# system_electric_diagram__1.net
KiCad netlist of a schematic drawn in Altium Designer
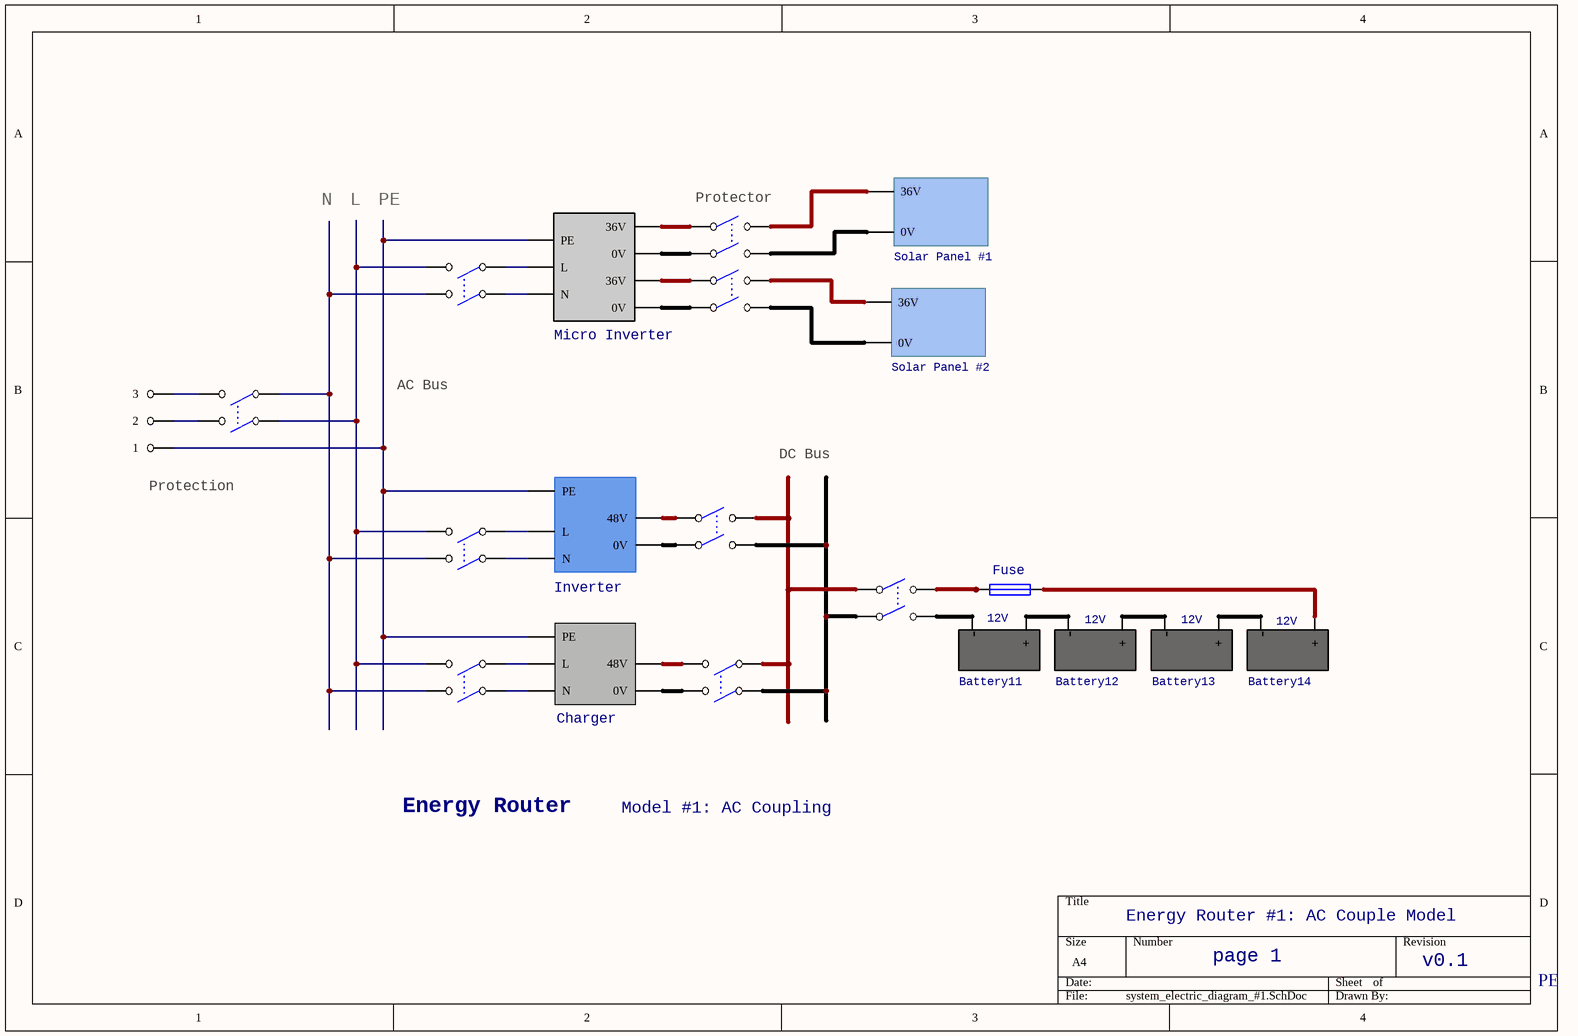
[diagram p0: system_electric_diagram_#1.SchDoc]

(export (version "E")
  (design (tool "Eeschema 10.0.6"))
  (components
    (comp (ref "Battery11") (value "12V") (libsource (lib "0_Schlib-电源柜") (part "1_BAT_12V")))
    (comp (ref "Battery12") (value "12V") (libsource (lib "0_Schlib-电源柜") (part "1_BAT_12V")))
    (comp (ref "Battery13") (value "12V") (libsource (lib "0_Schlib-电源柜") (part "1_BAT_12V")))
    (comp (ref "Battery14") (value "12V") (libsource (lib "0_Schlib-电源柜") (part "1_BAT_12V")))
    (comp (ref "F11") (value "Fuse") (footprint "FUSE1") (libsource (lib "常用元件库") (part "FUSE")))
    (comp (ref "JP01")
      (value "3 HEADER")
      (description "3 Pin Header")
      (libsource (lib "myzou") (part "3 HEADER"))
    )
    (comp (ref "K2") (value "Switch") (libsource (lib "开关") (part "SW-DPST")))
    (comp (ref "K3") (value "Switch") (libsource (lib "开关") (part "SW-DPST")))
    (comp (ref "K4") (value "Switch") (libsource (lib "开关") (part "SW-DPST")))
    (comp (ref "K5") (value "Switch") (libsource (lib "开关") (part "SW-DPST")))
    (comp (ref "K6") (value "Switch") (libsource (lib "开关") (part "SW-DPST")))
    (comp (ref "K7") (value "Switch") (libsource (lib "开关") (part "SW-DPST")))
    (comp (ref "K10") (value "Switch") (libsource (lib "开关") (part "SW-DPST")))
    (comp (ref "K11") (value "Switch") (libsource (lib "开关") (part "SW-DPST")))
    (comp (ref "K12") (value "Switch") (libsource (lib "开关") (part "SW-DPST")))
    (comp (ref "U1") (value "Micro Inverter") (libsource (lib "0_Schlib-电源柜") (part "11_Micro_Inverter_2")))
    (comp (ref "U2") (value "Inverter") (libsource (lib "0_Schlib-电源柜") (part "4_Inverter")))
    (comp (ref "U3") (value "Charger") (libsource (lib "0_Schlib-电源柜") (part "5_Charger_48V")))
    (comp (ref "U4") (value "Solar Panel #1") (libsource (lib "0_Schlib-电源柜") (part "10_Solar_Panel_36V")))
    (comp (ref "U5") (value "Solar Panel #2") (libsource (lib "0_Schlib-电源柜") (part "10_Solar_Panel_36V")))
  )
  (nets
    (net (code "1") (name "Net-(Battery11-+)") (class "Default")
      (node (ref "Battery11") (pin "2") (pinfunction "+_2") (pintype "passive"))
      (node (ref "Battery12") (pin "1") (pinfunction "-_1") (pintype "passive"))
    )
    (net (code "2") (name "Net-(Battery11--)") (class "Default")
      (node (ref "Battery11") (pin "1") (pinfunction "-_1") (pintype "passive"))
      (node (ref "K12") (pin "4") (pinfunction "4_4") (pintype "passive"))
    )
    (net (code "3") (name "Net-(Battery12-+)") (class "Default")
      (node (ref "Battery12") (pin "2") (pinfunction "+_2") (pintype "passive"))
      (node (ref "Battery13") (pin "1") (pinfunction "-_1") (pintype "passive"))
    )
    (net (code "4") (name "Net-(Battery13-+)") (class "Default")
      (node (ref "Battery13") (pin "2") (pinfunction "+_2") (pintype "passive"))
      (node (ref "Battery14") (pin "1") (pinfunction "-_1") (pintype "passive"))
    )
    (net (code "5") (name "Net-(Battery14-+)") (class "Default")
      (node (ref "Battery14") (pin "2") (pinfunction "+_2") (pintype "passive"))
      (node (ref "F11") (pin "2") (pinfunction "2_2") (pintype "passive"))
    )
    (net (code "6") (name "Net-(F11-Pad1)") (class "Default")
      (node (ref "F11") (pin "1") (pinfunction "1_1") (pintype "passive"))
      (node (ref "K12") (pin "2") (pinfunction "2_2") (pintype "passive"))
    )
    (net (code "7") (name "Net-(JP01-Pad2)") (class "Default")
      (node (ref "JP01") (pin "2") (pinfunction "2_2") (pintype "passive"))
      (node (ref "K10") (pin "2") (pinfunction "2_2") (pintype "passive"))
    )
    (net (code "8") (name "Net-(JP01-Pad3)") (class "Default")
      (node (ref "JP01") (pin "3") (pinfunction "3_3") (pintype "passive"))
      (node (ref "K10") (pin "4") (pinfunction "4_4") (pintype "passive"))
    )
    (net (code "9") (name "Net-(K4-Pad1)") (class "Default")
      (node (ref "K4") (pin "1") (pinfunction "1_1") (pintype "passive"))
      (node (ref "U1") (pin "7") (pinfunction "36V_7") (pintype "passive"))
    )
    (net (code "10") (name "Net-(K4-Pad3)") (class "Default")
      (node (ref "K4") (pin "3") (pinfunction "3_3") (pintype "passive"))
      (node (ref "U1") (pin "6") (pinfunction "0V_6") (pintype "passive"))
    )
    (net (code "11") (name "Net-(K5-Pad1)") (class "Default")
      (node (ref "K5") (pin "1") (pinfunction "1_1") (pintype "passive"))
      (node (ref "U1") (pin "5") (pinfunction "36V_5") (pintype "passive"))
    )
    (net (code "12") (name "Net-(K5-Pad3)") (class "Default")
      (node (ref "K5") (pin "3") (pinfunction "3_3") (pintype "passive"))
      (node (ref "U1") (pin "4") (pinfunction "0V_4") (pintype "passive"))
    )
    (net (code "13") (name "Net-(K10-Pad1)") (class "Default")
      (node (ref "K10") (pin "1") (pinfunction "1_1") (pintype "passive"))
      (node (ref "K11") (pin "4") (pinfunction "4_4") (pintype "passive"))
      (node (ref "K2") (pin "4") (pinfunction "4_4") (pintype "passive"))
      (node (ref "K3") (pin "4") (pinfunction "4_4") (pintype "passive"))
    )
    (net (code "14") (name "Net-(K10-Pad3)") (class "Default")
      (node (ref "K10") (pin "3") (pinfunction "3_3") (pintype "passive"))
      (node (ref "K11") (pin "2") (pinfunction "2_2") (pintype "passive"))
      (node (ref "K2") (pin "2") (pinfunction "2_2") (pintype "passive"))
      (node (ref "K3") (pin "2") (pinfunction "2_2") (pintype "passive"))
    )
    (net (code "15") (name "Net-(K12-Pad1)") (class "Default")
      (node (ref "K12") (pin "1") (pinfunction "1_1") (pintype "passive"))
      (node (ref "K6") (pin "2") (pinfunction "2_2") (pintype "passive"))
      (node (ref "K7") (pin "3") (pinfunction "3_3") (pintype "passive"))
    )
    (net (code "16") (name "Net-(K12-Pad3)") (class "Default")
      (node (ref "K12") (pin "3") (pinfunction "3_3") (pintype "passive"))
      (node (ref "K6") (pin "4") (pinfunction "4_4") (pintype "passive"))
      (node (ref "K7") (pin "1") (pinfunction "1_1") (pintype "passive"))
    )
    (net (code "17") (name "Net-(U1-L)") (class "Default")
      (node (ref "K11") (pin "3") (pinfunction "3_3") (pintype "passive"))
      (node (ref "U1") (pin "2") (pinfunction "L_2") (pintype "passive"))
    )
    (net (code "18") (name "Net-(U1-N)") (class "Default")
      (node (ref "K11") (pin "1") (pinfunction "1_1") (pintype "passive"))
      (node (ref "U1") (pin "1") (pinfunction "N_1") (pintype "passive"))
    )
    (net (code "19") (name "Net-(U1-PE)") (class "Default")
      (node (ref "JP01") (pin "1") (pinfunction "1_1") (pintype "passive"))
      (node (ref "U1") (pin "3") (pinfunction "PE_3") (pintype "passive"))
      (node (ref "U2") (pin "3") (pinfunction "PE_3") (pintype "passive"))
      (node (ref "U3") (pin "3") (pinfunction "PE_3") (pintype "passive"))
    )
    (net (code "20") (name "Net-(U2-0V)") (class "Default")
      (node (ref "K6") (pin "3") (pinfunction "3_3") (pintype "passive"))
      (node (ref "U2") (pin "4") (pinfunction "0V_4") (pintype "passive"))
    )
    (net (code "21") (name "Net-(U2-48V)") (class "Default")
      (node (ref "K6") (pin "1") (pinfunction "1_1") (pintype "passive"))
      (node (ref "U2") (pin "5") (pinfunction "48V_5") (pintype "passive"))
    )
    (net (code "22") (name "Net-(U2-L)") (class "Default")
      (node (ref "K2") (pin "3") (pinfunction "3_3") (pintype "passive"))
      (node (ref "U2") (pin "2") (pinfunction "L_2") (pintype "passive"))
    )
    (net (code "23") (name "Net-(U2-N)") (class "Default")
      (node (ref "K2") (pin "1") (pinfunction "1_1") (pintype "passive"))
      (node (ref "U2") (pin "1") (pinfunction "N_1") (pintype "passive"))
    )
    (net (code "24") (name "Net-(U3-0V)") (class "Default")
      (node (ref "K7") (pin "2") (pinfunction "2_2") (pintype "passive"))
      (node (ref "U3") (pin "4") (pinfunction "0V_4") (pintype "passive"))
    )
    (net (code "25") (name "Net-(U3-48V)") (class "Default")
      (node (ref "K7") (pin "4") (pinfunction "4_4") (pintype "passive"))
      (node (ref "U3") (pin "5") (pinfunction "48V_5") (pintype "passive"))
    )
    (net (code "26") (name "Net-(U3-L)") (class "Default")
      (node (ref "K3") (pin "3") (pinfunction "3_3") (pintype "passive"))
      (node (ref "U3") (pin "2") (pinfunction "L_2") (pintype "passive"))
    )
    (net (code "27") (name "Net-(U3-N)") (class "Default")
      (node (ref "K3") (pin "1") (pinfunction "1_1") (pintype "passive"))
      (node (ref "U3") (pin "1") (pinfunction "N_1") (pintype "passive"))
    )
    (net (code "28") (name "Net-(U4-0V)") (class "Default")
      (node (ref "K4") (pin "4") (pinfunction "4_4") (pintype "passive"))
      (node (ref "U4") (pin "1") (pinfunction "0V_1") (pintype "passive"))
    )
    (net (code "29") (name "Net-(U4-36V)") (class "Default")
      (node (ref "K4") (pin "2") (pinfunction "2_2") (pintype "passive"))
      (node (ref "U4") (pin "2") (pinfunction "36V_2") (pintype "passive"))
    )
    (net (code "30") (name "Net-(U5-0V)") (class "Default")
      (node (ref "K5") (pin "4") (pinfunction "4_4") (pintype "passive"))
      (node (ref "U5") (pin "1") (pinfunction "0V_1") (pintype "passive"))
    )
    (net (code "31") (name "Net-(U5-36V)") (class "Default")
      (node (ref "K5") (pin "2") (pinfunction "2_2") (pintype "passive"))
      (node (ref "U5") (pin "2") (pinfunction "36V_2") (pintype "passive"))
    )
  )
)
